# RPI_HAT_AMP_TAS5756_02.net
KiCad netlist of a schematic drawn in Altium Designer
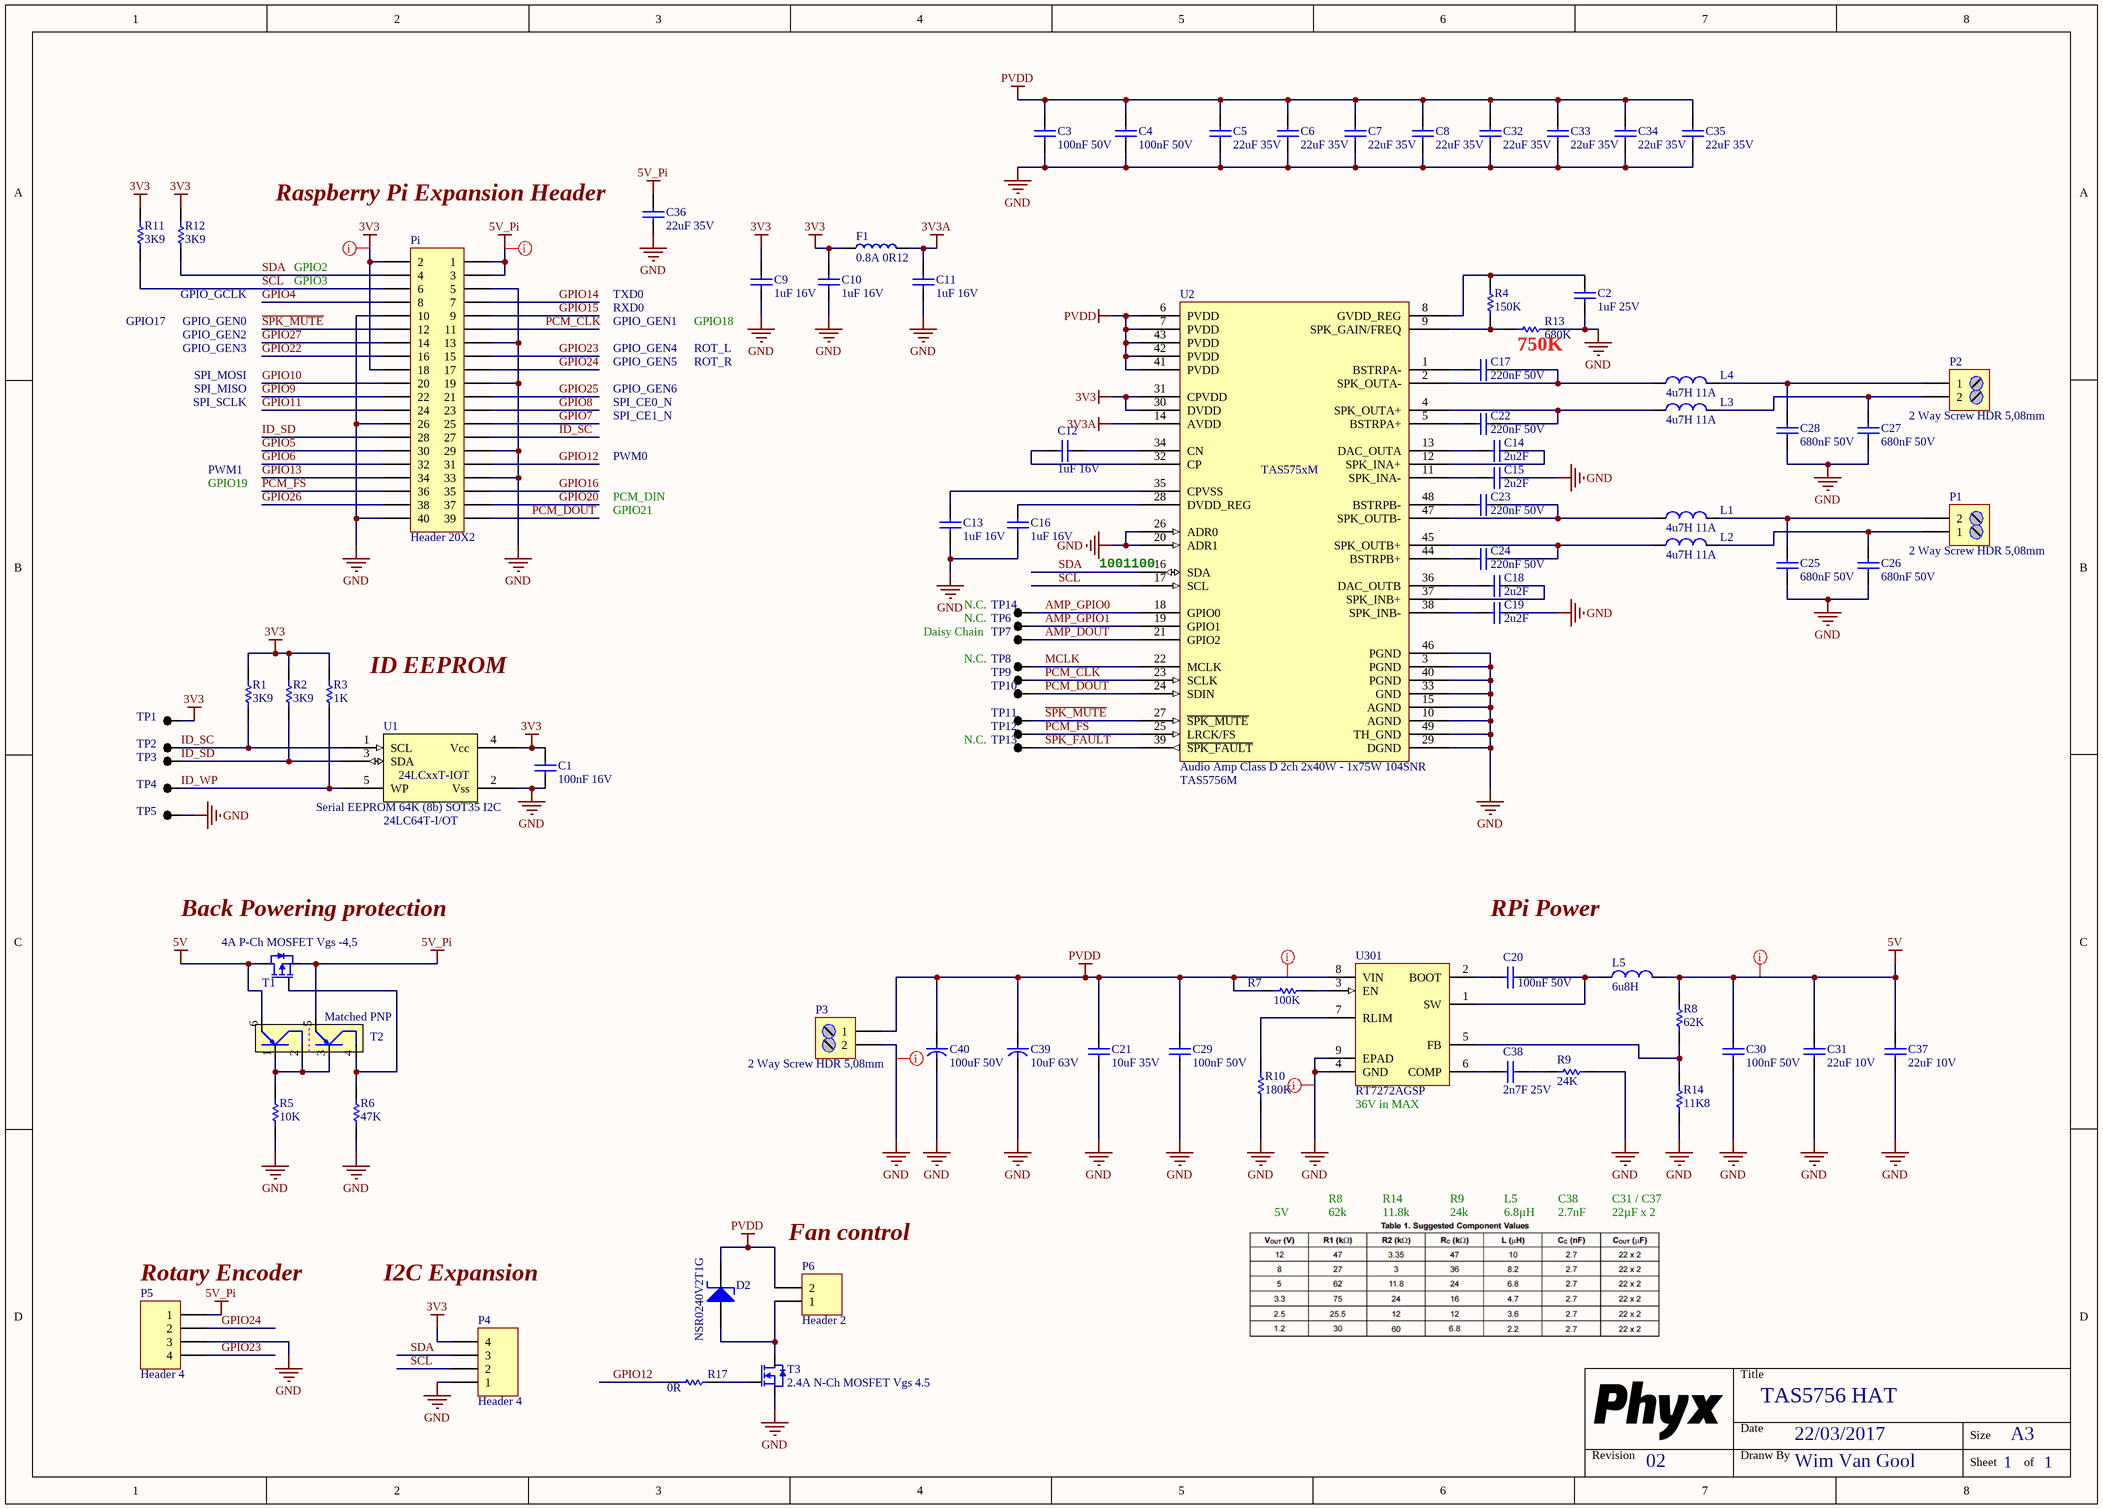
[diagram p0: RPI_HAT_AMP_TAS5756_02.SchDoc]

(export (version "E")
  (design (tool "Eeschema 10.0.6"))
  (components
    (comp (ref "C1")
      (value "100nF 16V")
      (footprint "C0603_N")
      (description "Capacitor Ceramic")
      (fields (field (name "Comment") "CAP_CERAMIC"))
      (libsource (lib "Phyx_Components") (part "CAP_CERAMIC"))
    )
    (comp (ref "C2")
      (value "1uF 25V")
      (footprint "C0805_N")
      (description "Capacitor Ceramic")
      (fields (field (name "Comment") "CAP_CERAMIC"))
      (libsource (lib "Phyx_Components") (part "CAP_CERAMIC"))
    )
    (comp (ref "C3")
      (value "100nF 50V")
      (footprint "C0805_N")
      (description "Capacitor Ceramic")
      (fields (field (name "Comment") "CAP_CERAMIC"))
      (libsource (lib "Phyx_Components") (part "CAP_CERAMIC"))
    )
    (comp (ref "C4")
      (value "100nF 50V")
      (footprint "C0805_N")
      (description "Capacitor Ceramic")
      (fields (field (name "Comment") "CAP_CERAMIC"))
      (libsource (lib "Phyx_Components") (part "CAP_CERAMIC"))
    )
    (comp (ref "C5")
      (value "22uF 35V")
      (footprint "C1206_N")
      (description "Capacitor Ceramic")
      (fields (field (name "Comment") "CAP_CERAMIC"))
      (libsource (lib "Phyx_Components") (part "CAP_CERAMIC"))
    )
    (comp (ref "C6")
      (value "22uF 35V")
      (footprint "C1206_N")
      (description "Capacitor Ceramic")
      (fields (field (name "Comment") "CAP_CERAMIC"))
      (libsource (lib "Phyx_Components") (part "CAP_CERAMIC"))
    )
    (comp (ref "C7")
      (value "22uF 35V")
      (footprint "C1206_N")
      (description "Capacitor Ceramic")
      (fields (field (name "Comment") "CAP_CERAMIC"))
      (libsource (lib "Phyx_Components") (part "CAP_CERAMIC"))
    )
    (comp (ref "C8")
      (value "22uF 35V")
      (footprint "C1206_N")
      (description "Capacitor Ceramic")
      (fields (field (name "Comment") "CAP_CERAMIC"))
      (libsource (lib "Phyx_Components") (part "CAP_CERAMIC"))
    )
    (comp (ref "C9")
      (value "1uF 16V")
      (footprint "C0603_N")
      (description "Capacitor Ceramic")
      (fields (field (name "Comment") "CAP_CERAMIC"))
      (libsource (lib "Phyx_Components") (part "CAP_CERAMIC"))
    )
    (comp (ref "C10")
      (value "1uF 16V")
      (footprint "C0603_N")
      (description "Capacitor Ceramic")
      (fields (field (name "Comment") "CAP_CERAMIC"))
      (libsource (lib "Phyx_Components") (part "CAP_CERAMIC"))
    )
    (comp (ref "C11")
      (value "1uF 16V")
      (footprint "C0603_N")
      (description "Capacitor Ceramic")
      (fields (field (name "Comment") "CAP_CERAMIC"))
      (libsource (lib "Phyx_Components") (part "CAP_CERAMIC"))
    )
    (comp (ref "C12")
      (value "1uF 16V")
      (footprint "C0603_N")
      (description "Capacitor Ceramic")
      (fields (field (name "Comment") "CAP_CERAMIC"))
      (libsource (lib "Phyx_Components") (part "CAP_CERAMIC"))
    )
    (comp (ref "C13")
      (value "1uF 16V")
      (footprint "C0603_N")
      (description "Capacitor Ceramic")
      (fields (field (name "Comment") "CAP_CERAMIC"))
      (libsource (lib "Phyx_Components") (part "CAP_CERAMIC"))
    )
    (comp (ref "C14")
      (value "2u2F")
      (footprint "C0805_N")
      (description "Capacitor Ceramic")
      (fields (field (name "Comment") "CAP_CERAMIC"))
      (libsource (lib "Phyx_Components") (part "CAP_CERAMIC"))
    )
    (comp (ref "C15")
      (value "2u2F")
      (footprint "C0805_N")
      (description "Capacitor Ceramic")
      (fields (field (name "Comment") "CAP_CERAMIC"))
      (libsource (lib "Phyx_Components") (part "CAP_CERAMIC"))
    )
    (comp (ref "C16")
      (value "1uF 16V")
      (footprint "C0603_N")
      (description "Capacitor Ceramic")
      (fields (field (name "Comment") "CAP_CERAMIC"))
      (libsource (lib "Phyx_Components") (part "CAP_CERAMIC"))
    )
    (comp (ref "C17")
      (value "220nF 50V")
      (footprint "C0805_N")
      (description "Capacitor Ceramic")
      (fields (field (name "Comment") "CAP_CERAMIC"))
      (libsource (lib "Phyx_Components") (part "CAP_CERAMIC"))
    )
    (comp (ref "C18")
      (value "2u2F")
      (footprint "C0805_N")
      (description "Capacitor Ceramic")
      (fields (field (name "Comment") "CAP_CERAMIC"))
      (libsource (lib "Phyx_Components") (part "CAP_CERAMIC"))
    )
    (comp (ref "C19")
      (value "2u2F")
      (footprint "C0805_N")
      (description "Capacitor Ceramic")
      (fields (field (name "Comment") "CAP_CERAMIC"))
      (libsource (lib "Phyx_Components") (part "CAP_CERAMIC"))
    )
    (comp (ref "C20")
      (value "100nF 50V")
      (footprint "C0603_N")
      (description "Capacitor Ceramic")
      (fields (field (name "Comment") "CAP_CERAMIC"))
      (libsource (lib "Phyx_Components") (part "CAP_CERAMIC"))
    )
    (comp (ref "C21")
      (value "10uF 35V")
      (footprint "C1206_N")
      (description "CAP # 10uF 35V 1206 X5R")
      (fields (field (name "Comment") "CAP_CERAMIC"))
      (libsource (lib "Phyx_Components") (part "CAP_CERAMIC"))
    )
    (comp (ref "C22")
      (value "220nF 50V")
      (footprint "C0805_N")
      (description "Capacitor Ceramic")
      (fields (field (name "Comment") "CAP_CERAMIC"))
      (libsource (lib "Phyx_Components") (part "CAP_CERAMIC"))
    )
    (comp (ref "C23")
      (value "220nF 50V")
      (footprint "C0805_N")
      (description "Capacitor Ceramic")
      (fields (field (name "Comment") "CAP_CERAMIC"))
      (libsource (lib "Phyx_Components") (part "CAP_CERAMIC"))
    )
    (comp (ref "C24")
      (value "220nF 50V")
      (footprint "C0805_N")
      (description "Capacitor Ceramic")
      (fields (field (name "Comment") "CAP_CERAMIC"))
      (libsource (lib "Phyx_Components") (part "CAP_CERAMIC"))
    )
    (comp (ref "C25")
      (value "680nF 50V")
      (footprint "C0805_N")
      (description "Capacitor Ceramic")
      (fields (field (name "Comment") "CAP_CERAMIC"))
      (libsource (lib "Phyx_Components") (part "CAP_CERAMIC"))
    )
    (comp (ref "C26")
      (value "680nF 50V")
      (footprint "C0805_N")
      (description "Capacitor Ceramic")
      (fields (field (name "Comment") "CAP_CERAMIC"))
      (libsource (lib "Phyx_Components") (part "CAP_CERAMIC"))
    )
    (comp (ref "C27")
      (value "680nF 50V")
      (footprint "C0805_N")
      (description "Capacitor Ceramic")
      (fields (field (name "Comment") "CAP_CERAMIC"))
      (libsource (lib "Phyx_Components") (part "CAP_CERAMIC"))
    )
    (comp (ref "C28")
      (value "680nF 50V")
      (footprint "C0805_N")
      (description "Capacitor Ceramic")
      (fields (field (name "Comment") "CAP_CERAMIC"))
      (libsource (lib "Phyx_Components") (part "CAP_CERAMIC"))
    )
    (comp (ref "C29")
      (value "100nF 50V")
      (footprint "C0603_N")
      (description "Capacitor Ceramic")
      (fields (field (name "Comment") "CAP_CERAMIC"))
      (libsource (lib "Phyx_Components") (part "CAP_CERAMIC"))
    )
    (comp (ref "C30")
      (value "100nF 50V")
      (footprint "C0603_N")
      (description "Capacitor Ceramic")
      (fields (field (name "Comment") "CAP_CERAMIC"))
      (libsource (lib "Phyx_Components") (part "CAP_CERAMIC"))
    )
    (comp (ref "C31")
      (value "22uF 10V")
      (footprint "C1210_N")
      (description "Capacitor Ceramic")
      (fields (field (name "Comment") "CAP_CERAMIC"))
      (libsource (lib "Phyx_Components") (part "CAP_CERAMIC"))
    )
    (comp (ref "C32")
      (value "22uF 35V")
      (footprint "C1206_N")
      (description "Capacitor Ceramic")
      (fields (field (name "Comment") "CAP_CERAMIC"))
      (libsource (lib "Phyx_Components") (part "CAP_CERAMIC"))
    )
    (comp (ref "C33")
      (value "22uF 35V")
      (footprint "C1206_N")
      (description "Capacitor Ceramic")
      (fields (field (name "Comment") "CAP_CERAMIC"))
      (libsource (lib "Phyx_Components") (part "CAP_CERAMIC"))
    )
    (comp (ref "C34")
      (value "22uF 35V")
      (footprint "C1206_N")
      (description "Capacitor Ceramic")
      (fields (field (name "Comment") "CAP_CERAMIC"))
      (libsource (lib "Phyx_Components") (part "CAP_CERAMIC"))
    )
    (comp (ref "C35")
      (value "22uF 35V")
      (footprint "C1206_N")
      (description "Capacitor Ceramic")
      (fields (field (name "Comment") "CAP_CERAMIC"))
      (libsource (lib "Phyx_Components") (part "CAP_CERAMIC"))
    )
    (comp (ref "C36")
      (value "22uF 35V")
      (footprint "C1206_N")
      (description "Capacitor Ceramic")
      (fields (field (name "Comment") "CAP_CERAMIC"))
      (libsource (lib "Phyx_Components") (part "CAP_CERAMIC"))
    )
    (comp (ref "C37")
      (value "22uF 10V")
      (footprint "C1210_N")
      (description "Capacitor Ceramic")
      (fields (field (name "Comment") "CAP_CERAMIC"))
      (libsource (lib "Phyx_Components") (part "CAP_CERAMIC"))
    )
    (comp (ref "C38")
      (value "2n7F 25V")
      (footprint "C0603_N")
      (description "Capacitor Ceramic")
      (fields (field (name "Comment") "CAP_CERAMIC"))
      (libsource (lib "Phyx_Components") (part "CAP_CERAMIC"))
    )
    (comp (ref "C39")
      (value "10uF 63V")
      (footprint "C_5x11_2mm")
      (description "CAP 10uF 63V 5x11mm")
      (fields (field (name "Comment") "CAP_POL"))
      (libsource (lib "Phyx_Components") (part "CAP_POL"))
    )
    (comp (ref "C40")
      (value "100uF 50V")
      (footprint "C_8x11.5_3.5mm")
      (description "CAP 100uF 50V 8x11mm")
      (fields (field (name "Comment") "CAP_POL"))
      (libsource (lib "Phyx_Components") (part "CAP_POL"))
    )
    (comp (ref "D2")
      (value "NSR0240V2T1G")
      (footprint "ON_SOD-523")
      (description "=Description")
      (fields (field (name "Comment") "NSR0240V2T1G Schottky ULTRAFAST, 200MA, 40V"))
      (libsource (lib "Phyx_Components") (part "Schottky_CA"))
    )
    (comp (ref "F1")
      (value "0.8A 0R12")
      (footprint "L0805")
      (fields (field (name "Comment") "FERRITE"))
      (libsource (lib "Phyx_Components") (part "FERRITE"))
    )
    (comp (ref "L1")
      (value "4u7H 11A")
      (footprint "XAL6060-472")
      (fields (field (name "Comment") "XAL6060-472MEC"))
      (libsource (lib "Phyx_Components") (part "INDUCTOR"))
    )
    (comp (ref "L2")
      (value "4u7H 11A")
      (footprint "XAL6060-472")
      (fields (field (name "Comment") "XAL6060-472MEC"))
      (libsource (lib "Phyx_Components") (part "INDUCTOR"))
    )
    (comp (ref "L3")
      (value "4u7H 11A")
      (footprint "XAL6060-472")
      (fields (field (name "Comment") "XAL6060-472MEC"))
      (libsource (lib "Phyx_Components") (part "INDUCTOR"))
    )
    (comp (ref "L4")
      (value "4u7H 11A")
      (footprint "XAL6060-472")
      (fields (field (name "Comment") "XAL6060-472MEC"))
      (libsource (lib "Phyx_Components") (part "INDUCTOR"))
    )
    (comp (ref "L5")
      (value "6u8H")
      (footprint "SNL_SWPA4020")
      (fields (field (name "Comment") "SWPA4020S6R8MT"))
      (libsource (lib "Phyx_Components") (part "INDUCTOR"))
    )
    (comp (ref "P1")
      (value "2 Way Screw HDR 5,08mm")
      (footprint "TERM_BLK-0508-2-90")
      (libsource (lib "") (part "TERM_BLCK_2_2"))
    )
    (comp (ref "P2")
      (value "2 Way Screw HDR 5,08mm")
      (footprint "TERM_BLK-0508-2-90")
      (libsource (lib "") (part "TERM_BLCK_2_1"))
    )
    (comp (ref "P3")
      (value "2 Way Screw HDR 5,08mm")
      (footprint "TERM_BLK-0508-2-90")
      (libsource (lib "Phyx_Components") (part "TERM_BLCK_2"))
    )
    (comp (ref "P4") (value "Header 4") (footprint "HDR1X4") (libsource (lib "") (part "Header 4_1")))
    (comp (ref "P5")
      (value "Header 4")
      (footprint "HDR1X4")
      (libsource (lib "Phyx_Components") (part "Header 4"))
    )
    (comp (ref "P6")
      (value "Header 2")
      (footprint "HDR1X2")
      (libsource (lib "Phyx_Components") (part "Header 2"))
    )
    (comp (ref "Pi")
      (value "Header 20X2")
      (footprint "RCPT2X20")
      (description "=Description")
      (libsource (lib "Phyx_Components") (part "Header 20X2"))
    )
    (comp (ref "R1")
      (value "3K9")
      (footprint "R0603_N")
      (fields (field (name "Comment") "RESISTOR"))
      (libsource (lib "Phyx_Components") (part "RESISTOR"))
    )
    (comp (ref "R2")
      (value "3K9")
      (footprint "R0603_N")
      (fields (field (name "Comment") "RESISTOR"))
      (libsource (lib "Phyx_Components") (part "RESISTOR"))
    )
    (comp (ref "R3")
      (value "1K")
      (footprint "R0603_N")
      (fields (field (name "Comment") "RESISTOR"))
      (libsource (lib "Phyx_Components") (part "RESISTOR"))
    )
    (comp (ref "R4")
      (value "150K")
      (footprint "R0603_N")
      (fields (field (name "Comment") "RESISTOR"))
      (libsource (lib "Phyx_Components") (part "RESISTOR"))
    )
    (comp (ref "R5")
      (value "10K")
      (footprint "R0603_N")
      (fields (field (name "Comment") "RESISTOR"))
      (libsource (lib "Phyx_Components") (part "RESISTOR"))
    )
    (comp (ref "R6")
      (value "47K")
      (footprint "R0603_N")
      (fields (field (name "Comment") "RESISTOR"))
      (libsource (lib "Phyx_Components") (part "RESISTOR"))
    )
    (comp (ref "R7")
      (value "100K")
      (footprint "R0603_N")
      (fields (field (name "Comment") "RESISTOR"))
      (libsource (lib "Phyx_Components") (part "RESISTOR"))
    )
    (comp (ref "R8")
      (value "62K")
      (footprint "R0603_N")
      (fields (field (name "Comment") "RESISTOR"))
      (libsource (lib "Phyx_Components") (part "RESISTOR"))
    )
    (comp (ref "R9")
      (value "24K")
      (footprint "R0603_N")
      (fields (field (name "Comment") "RESISTOR"))
      (libsource (lib "Phyx_Components") (part "RESISTOR"))
    )
    (comp (ref "R10")
      (value "180K")
      (footprint "R0603_N")
      (fields (field (name "Comment") "RESISTOR"))
      (libsource (lib "Phyx_Components") (part "RESISTOR"))
    )
    (comp (ref "R11")
      (value "3K9")
      (footprint "R0603_N")
      (fields (field (name "Comment") "RESISTOR"))
      (libsource (lib "Phyx_Components") (part "RESISTOR"))
    )
    (comp (ref "R12")
      (value "3K9")
      (footprint "R0603_N")
      (fields (field (name "Comment") "RESISTOR"))
      (libsource (lib "Phyx_Components") (part "RESISTOR"))
    )
    (comp (ref "R13")
      (value "680K")
      (footprint "R0603_N")
      (fields (field (name "Comment") "RESISTOR"))
      (libsource (lib "Phyx_Components") (part "RESISTOR"))
    )
    (comp (ref "R14")
      (value "11K8")
      (footprint "R0603_N")
      (fields (field (name "Comment") "RESISTOR"))
      (libsource (lib "Phyx_Components") (part "RESISTOR"))
    )
    (comp (ref "R17")
      (value "0R")
      (footprint "R0603_N")
      (fields (field (name "Comment") "RESISTOR"))
      (libsource (lib "Phyx_Components") (part "RESISTOR"))
    )
    (comp (ref "T1")
      (value "4A P-Ch MOSFET Vgs -4,5")
      (footprint "SOT23-3")
      (description "=Description")
      (libsource (lib "Phyx_Components") (part "P_MOSFET_GSD"))
    )
    (comp (ref "T2")
      (value "Matched PNP")
      (footprint "SOT23-6")
      (libsource (lib "Phyx_Components") (part "DMMT5401"))
    )
    (comp (ref "T3")
      (value "2.4A N-Ch MOSFET Vgs 4.5")
      (footprint "SOT23-3")
      (libsource (lib "Phyx_Components") (part "N_MOSFET_GSD"))
    )
    (comp (ref "TP1")
      (value "TEST_PAD")
      (footprint "TP_1.2mm_0.6mm")
      (libsource (lib "Phyx_Components") (part "TEST_PAD"))
    )
    (comp (ref "TP2")
      (value "TEST_PAD")
      (footprint "TP_1.2mm_0.6mm")
      (libsource (lib "Phyx_Components") (part "TEST_PAD"))
    )
    (comp (ref "TP3")
      (value "TEST_PAD")
      (footprint "TP_1.2mm_0.6mm")
      (libsource (lib "Phyx_Components") (part "TEST_PAD"))
    )
    (comp (ref "TP4")
      (value "TEST_PAD")
      (footprint "TP_1.2mm_0.6mm")
      (libsource (lib "Phyx_Components") (part "TEST_PAD"))
    )
    (comp (ref "TP5")
      (value "TEST_PAD")
      (footprint "TP_1.2mm_0.6mm")
      (libsource (lib "Phyx_Components") (part "TEST_PAD"))
    )
    (comp (ref "TP6")
      (value "TEST_PAD")
      (footprint "TP_0.4mm")
      (libsource (lib "Phyx_Components") (part "TEST_PAD"))
    )
    (comp (ref "TP7")
      (value "TEST_PAD")
      (footprint "TP_1.2mm_0.6mm")
      (libsource (lib "Phyx_Components") (part "TEST_PAD"))
    )
    (comp (ref "TP8")
      (value "TEST_PAD")
      (footprint "TP_0.4mm")
      (libsource (lib "Phyx_Components") (part "TEST_PAD"))
    )
    (comp (ref "TP9")
      (value "TEST_PAD")
      (footprint "TP_0.4mm")
      (libsource (lib "Phyx_Components") (part "TEST_PAD"))
    )
    (comp (ref "TP10")
      (value "TEST_PAD")
      (footprint "TP_1.2mm_0.6mm")
      (libsource (lib "Phyx_Components") (part "TEST_PAD"))
    )
    (comp (ref "TP11")
      (value "TEST_PAD")
      (footprint "TP_0.4mm")
      (libsource (lib "Phyx_Components") (part "TEST_PAD"))
    )
    (comp (ref "TP12")
      (value "TEST_PAD")
      (footprint "TP_0.4mm")
      (libsource (lib "Phyx_Components") (part "TEST_PAD"))
    )
    (comp (ref "TP13")
      (value "TEST_PAD")
      (footprint "TP_0.4mm")
      (libsource (lib "Phyx_Components") (part "TEST_PAD"))
    )
    (comp (ref "TP14")
      (value "TEST_PAD")
      (footprint "TP_0.4mm")
      (libsource (lib "Phyx_Components") (part "TEST_PAD"))
    )
    (comp (ref "U1")
      (value "Serial EEPROM 64K (8b) SOT35 I2C")
      (footprint "SOT23-5")
      (description "=Description")
      (fields (field (name "ALTIUM_VALUE") "24LC64T-I/OT"))
      (libsource (lib "Phyx_Components") (part "24LCxxT-IOT"))
    )
    (comp (ref "U2")
      (value "Audio Amp Class D 2ch 2x40W - 1x75W 104SNR")
      (footprint "TI-DCA-R-PDSO-G48")
      (description "=Description")
      (fields (field (name "ALTIUM_VALUE") "TAS5756M"))
      (libsource (lib "Phyx_Components") (part "TAS575xM"))
    )
    (comp (ref "U301")
      (value "RT7272AGSP")
      (footprint "SOIC_N_8_TH")
      (description "=Description")
      (fields (field (name "Comment") "Buck 3A 36Vin sync"))
      (libsource (lib "Phyx_Components") (part "RT7272xGSP"))
    )
  )
  (nets
    (net (code "1") (name "/AMP_DOUT") (class "Default")
      (node (ref "TP7") (pin "1") (pinfunction "1_1") (pintype "passive"))
      (node (ref "U2") (pin "21") (pinfunction "GPIO2_21") (pintype "passive"))
    )
    (net (code "2") (name "/AMP_GPIO0") (class "Default")
      (node (ref "TP14") (pin "1") (pinfunction "1_1") (pintype "passive"))
      (node (ref "U2") (pin "18") (pinfunction "GPIO0_18") (pintype "passive"))
    )
    (net (code "3") (name "/AMP_GPIO1") (class "Default")
      (node (ref "TP6") (pin "1") (pinfunction "1_1") (pintype "passive"))
      (node (ref "U2") (pin "19") (pinfunction "GPIO1_19") (pintype "passive"))
    )
    (net (code "4") (name "/GPIO4") (class "Default")
      (node (ref "Pi") (pin "8") (pinfunction "8_8") (pintype "passive"))
    )
    (net (code "5") (name "/GPIO5") (class "Default")
      (node (ref "Pi") (pin "30") (pinfunction "30_30") (pintype "passive"))
    )
    (net (code "6") (name "/GPIO6") (class "Default")
      (node (ref "Pi") (pin "32") (pinfunction "32_32") (pintype "passive"))
    )
    (net (code "7") (name "/GPIO7") (class "Default")
      (node (ref "Pi") (pin "25") (pinfunction "25_25") (pintype "passive"))
    )
    (net (code "8") (name "/GPIO8") (class "Default")
      (node (ref "Pi") (pin "23") (pinfunction "23_23") (pintype "passive"))
    )
    (net (code "9") (name "/GPIO9") (class "Default")
      (node (ref "Pi") (pin "22") (pinfunction "22_22") (pintype "passive"))
    )
    (net (code "10") (name "/GPIO10") (class "Default")
      (node (ref "Pi") (pin "20") (pinfunction "20_20") (pintype "passive"))
    )
    (net (code "11") (name "/GPIO11") (class "Default")
      (node (ref "Pi") (pin "24") (pinfunction "24_24") (pintype "passive"))
    )
    (net (code "12") (name "/GPIO12") (class "Default")
      (node (ref "Pi") (pin "31") (pinfunction "31_31") (pintype "passive"))
      (node (ref "R17") (pin "2") (pinfunction "2_2") (pintype "passive"))
    )
    (net (code "13") (name "/GPIO13") (class "Default")
      (node (ref "Pi") (pin "34") (pinfunction "34_34") (pintype "passive"))
    )
    (net (code "14") (name "/GPIO14") (class "Default")
      (node (ref "Pi") (pin "7") (pinfunction "7_7") (pintype "passive"))
    )
    (net (code "15") (name "/GPIO15") (class "Default")
      (node (ref "Pi") (pin "9") (pinfunction "9_9") (pintype "passive"))
    )
    (net (code "16") (name "/GPIO16") (class "Default")
      (node (ref "Pi") (pin "35") (pinfunction "35_35") (pintype "passive"))
    )
    (net (code "17") (name "/GPIO20") (class "Default")
      (node (ref "Pi") (pin "37") (pinfunction "37_37") (pintype "passive"))
    )
    (net (code "18") (name "/GPIO22") (class "Default")
      (node (ref "Pi") (pin "16") (pinfunction "16_16") (pintype "passive"))
    )
    (net (code "19") (name "/GPIO23") (class "Default")
      (node (ref "P5") (pin "4") (pinfunction "4_4") (pintype "passive"))
      (node (ref "Pi") (pin "15") (pinfunction "15_15") (pintype "passive"))
    )
    (net (code "20") (name "/GPIO24") (class "Default")
      (node (ref "P5") (pin "2") (pinfunction "2_2") (pintype "passive"))
      (node (ref "Pi") (pin "17") (pinfunction "17_17") (pintype "passive"))
    )
    (net (code "21") (name "/GPIO25") (class "Default")
      (node (ref "Pi") (pin "21") (pinfunction "21_21") (pintype "passive"))
    )
    (net (code "22") (name "/GPIO26") (class "Default")
      (node (ref "Pi") (pin "38") (pinfunction "38_38") (pintype "passive"))
    )
    (net (code "23") (name "/GPIO27") (class "Default")
      (node (ref "Pi") (pin "14") (pinfunction "14_14") (pintype "passive"))
    )
    (net (code "24") (name "/ID_SC") (class "Default")
      (node (ref "Pi") (pin "27") (pinfunction "27_27") (pintype "passive"))
      (node (ref "R1") (pin "2") (pinfunction "2_2") (pintype "passive"))
      (node (ref "TP2") (pin "1") (pinfunction "1_1") (pintype "passive"))
      (node (ref "U1") (pin "1") (pinfunction "SCL_1") (pintype "input"))
    )
    (net (code "25") (name "/ID_SD") (class "Default")
      (node (ref "Pi") (pin "28") (pinfunction "28_28") (pintype "passive"))
      (node (ref "R2") (pin "2") (pinfunction "2_2") (pintype "passive"))
      (node (ref "TP3") (pin "1") (pinfunction "1_1") (pintype "passive"))
      (node (ref "U1") (pin "3") (pinfunction "SDA_3") (pintype "bidirectional"))
    )
    (net (code "26") (name "/ID_WP") (class "Default")
      (node (ref "R3") (pin "2") (pinfunction "2_2") (pintype "passive"))
      (node (ref "TP4") (pin "1") (pinfunction "1_1") (pintype "passive"))
      (node (ref "U1") (pin "5") (pinfunction "WP_5") (pintype "passive"))
    )
    (net (code "27") (name "/MCLK") (class "Default")
      (node (ref "TP8") (pin "1") (pinfunction "1_1") (pintype "passive"))
      (node (ref "U2") (pin "22") (pinfunction "MCLK_22") (pintype "passive"))
    )
    (net (code "28") (name "/PCM_CLK") (class "Default")
      (node (ref "Pi") (pin "11") (pinfunction "11_11") (pintype "passive"))
      (node (ref "TP9") (pin "1") (pinfunction "1_1") (pintype "passive"))
      (node (ref "U2") (pin "23") (pinfunction "SCLK_23") (pintype "input"))
    )
    (net (code "29") (name "/PCM_DOUT") (class "Default")
      (node (ref "Pi") (pin "39") (pinfunction "39_39") (pintype "passive"))
      (node (ref "TP10") (pin "1") (pinfunction "1_1") (pintype "passive"))
      (node (ref "U2") (pin "24") (pinfunction "SDIN_24") (pintype "input"))
    )
    (net (code "30") (name "/PCM_FS") (class "Default")
      (node (ref "Pi") (pin "36") (pinfunction "36_36") (pintype "passive"))
      (node (ref "TP12") (pin "1") (pinfunction "1_1") (pintype "passive"))
      (node (ref "U2") (pin "25") (pinfunction "LRCK/FS_25") (pintype "input"))
    )
    (net (code "31") (name "/SCL") (class "Default")
      (node (ref "P4") (pin "2") (pinfunction "2_2") (pintype "passive"))
      (node (ref "Pi") (pin "6") (pinfunction "6_6") (pintype "passive"))
      (node (ref "R11") (pin "2") (pinfunction "2_2") (pintype "passive"))
      (node (ref "U2") (pin "17") (pinfunction "SCL_17") (pintype "input"))
    )
    (net (code "32") (name "/SDA") (class "Default")
      (node (ref "P4") (pin "3") (pinfunction "3_3") (pintype "passive"))
      (node (ref "Pi") (pin "4") (pinfunction "4_4") (pintype "passive"))
      (node (ref "R12") (pin "2") (pinfunction "2_2") (pintype "passive"))
      (node (ref "U2") (pin "16") (pinfunction "SDA_16") (pintype "bidirectional"))
    )
    (net (code "33") (name "/~{SPK_FAULT}") (class "Default")
      (node (ref "TP13") (pin "1") (pinfunction "1_1") (pintype "passive"))
      (node (ref "U2") (pin "39") (pinfunction "~{SPK_FAULT}_39") (pintype "output"))
    )
    (net (code "34") (name "/~{SPK_MUTE}") (class "Default")
      (node (ref "Pi") (pin "12") (pinfunction "12_12") (pintype "passive"))
      (node (ref "TP11") (pin "1") (pinfunction "1_1") (pintype "passive"))
      (node (ref "U2") (pin "27") (pinfunction "~{SPK_MUTE}_27") (pintype "input"))
    )
    (net (code "35") (name "3V3") (class "Default")
      (node (ref "C1") (pin "1") (pinfunction "1_1") (pintype "passive"))
      (node (ref "C10") (pin "1") (pinfunction "1_1") (pintype "passive"))
      (node (ref "C9") (pin "1") (pinfunction "1_1") (pintype "passive"))
      (node (ref "F1") (pin "1") (pinfunction "1_1") (pintype "passive"))
      (node (ref "P4") (pin "4") (pinfunction "4_4") (pintype "passive"))
      (node (ref "Pi") (pin "18") (pinfunction "18_18") (pintype "passive"))
      (node (ref "Pi") (pin "2") (pinfunction "2_2") (pintype "passive"))
      (node (ref "R1") (pin "1") (pinfunction "1_1") (pintype "passive"))
      (node (ref "R11") (pin "1") (pinfunction "1_1") (pintype "passive"))
      (node (ref "R12") (pin "1") (pinfunction "1_1") (pintype "passive"))
      (node (ref "R2") (pin "1") (pinfunction "1_1") (pintype "passive"))
      (node (ref "R3") (pin "1") (pinfunction "1_1") (pintype "passive"))
      (node (ref "TP1") (pin "1") (pinfunction "1_1") (pintype "passive"))
      (node (ref "U1") (pin "4") (pinfunction "Vcc_4") (pintype "passive"))
      (node (ref "U2") (pin "30") (pinfunction "DVDD_30") (pintype "power_in"))
      (node (ref "U2") (pin "31") (pinfunction "CPVDD_31") (pintype "passive"))
    )
    (net (code "36") (name "3V3A") (class "Default")
      (node (ref "C11") (pin "1") (pinfunction "1_1") (pintype "passive"))
      (node (ref "F1") (pin "2") (pinfunction "2_2") (pintype "passive"))
      (node (ref "U2") (pin "14") (pinfunction "AVDD_14") (pintype "power_in"))
    )
    (net (code "37") (name "5V") (class "Default")
      (node (ref "C30") (pin "1") (pinfunction "1_1") (pintype "passive"))
      (node (ref "C31") (pin "1") (pinfunction "1_1") (pintype "passive"))
      (node (ref "C37") (pin "1") (pinfunction "1_1") (pintype "passive"))
      (node (ref "L5") (pin "2") (pinfunction "2_2") (pintype "passive"))
      (node (ref "R8") (pin "1") (pinfunction "1_1") (pintype "passive"))
      (node (ref "T1") (pin "3") (pinfunction "D_3") (pintype "passive"))
      (node (ref "T2") (pin "6") (pinfunction "E_6") (pintype "passive"))
    )
    (net (code "38") (name "5V_Pi") (class "Default")
      (node (ref "C36") (pin "1") (pinfunction "1_1") (pintype "passive"))
      (node (ref "P5") (pin "1") (pinfunction "1_1") (pintype "passive"))
      (node (ref "Pi") (pin "1") (pinfunction "1_1") (pintype "passive"))
      (node (ref "Pi") (pin "3") (pinfunction "3_3") (pintype "passive"))
      (node (ref "T1") (pin "2") (pinfunction "S_2") (pintype "passive"))
      (node (ref "T2") (pin "5") (pinfunction "E_5") (pintype "passive"))
    )
    (net (code "39") (name "GND") (class "Default")
      (node (ref "C1") (pin "2") (pinfunction "2_2") (pintype "passive"))
      (node (ref "C10") (pin "2") (pinfunction "2_2") (pintype "passive"))
      (node (ref "C11") (pin "2") (pinfunction "2_2") (pintype "passive"))
      (node (ref "C13") (pin "2") (pinfunction "2_2") (pintype "passive"))
      (node (ref "C15") (pin "1") (pinfunction "1_1") (pintype "passive"))
      (node (ref "C16") (pin "2") (pinfunction "2_2") (pintype "passive"))
      (node (ref "C19") (pin "1") (pinfunction "1_1") (pintype "passive"))
      (node (ref "C2") (pin "2") (pinfunction "2_2") (pintype "passive"))
      (node (ref "C21") (pin "2") (pinfunction "2_2") (pintype "passive"))
      (node (ref "C25") (pin "1") (pinfunction "1_1") (pintype "passive"))
      (node (ref "C26") (pin "1") (pinfunction "1_1") (pintype "passive"))
      (node (ref "C27") (pin "1") (pinfunction "1_1") (pintype "passive"))
      (node (ref "C28") (pin "1") (pinfunction "1_1") (pintype "passive"))
      (node (ref "C29") (pin "2") (pinfunction "2_2") (pintype "passive"))
      (node (ref "C3") (pin "2") (pinfunction "2_2") (pintype "passive"))
      (node (ref "C30") (pin "2") (pinfunction "2_2") (pintype "passive"))
      (node (ref "C31") (pin "2") (pinfunction "2_2") (pintype "passive"))
      (node (ref "C32") (pin "2") (pinfunction "2_2") (pintype "passive"))
      (node (ref "C33") (pin "2") (pinfunction "2_2") (pintype "passive"))
      (node (ref "C34") (pin "2") (pinfunction "2_2") (pintype "passive"))
      (node (ref "C35") (pin "2") (pinfunction "2_2") (pintype "passive"))
      (node (ref "C36") (pin "2") (pinfunction "2_2") (pintype "passive"))
      (node (ref "C37") (pin "2") (pinfunction "2_2") (pintype "passive"))
      (node (ref "C39") (pin "2") (pinfunction "2_2") (pintype "passive"))
      (node (ref "C4") (pin "2") (pinfunction "2_2") (pintype "passive"))
      (node (ref "C40") (pin "2") (pinfunction "2_2") (pintype "passive"))
      (node (ref "C5") (pin "2") (pinfunction "2_2") (pintype "passive"))
      (node (ref "C6") (pin "2") (pinfunction "2_2") (pintype "passive"))
      (node (ref "C7") (pin "2") (pinfunction "2_2") (pintype "passive"))
      (node (ref "C8") (pin "2") (pinfunction "2_2") (pintype "passive"))
      (node (ref "C9") (pin "2") (pinfunction "2_2") (pintype "passive"))
      (node (ref "P3") (pin "2") (pinfunction "2_2") (pintype "passive"))
      (node (ref "P4") (pin "1") (pinfunction "1_1") (pintype "passive"))
      (node (ref "P5") (pin "3") (pinfunction "3_3") (pintype "passive"))
      (node (ref "Pi") (pin "10") (pinfunction "10_10") (pintype "passive"))
      (node (ref "Pi") (pin "13") (pinfunction "13_13") (pintype "passive"))
      (node (ref "Pi") (pin "19") (pinfunction "19_19") (pintype "passive"))
      (node (ref "Pi") (pin "26") (pinfunction "26_26") (pintype "passive"))
      (node (ref "Pi") (pin "29") (pinfunction "29_29") (pintype "passive"))
      (node (ref "Pi") (pin "33") (pinfunction "33_33") (pintype "passive"))
      (node (ref "Pi") (pin "40") (pinfunction "40_40") (pintype "passive"))
      (node (ref "Pi") (pin "5") (pinfunction "5_5") (pintype "passive"))
      (node (ref "R10") (pin "2") (pinfunction "2_2") (pintype "passive"))
      (node (ref "R13") (pin "1") (pinfunction "1_1") (pintype "passive"))
      (node (ref "R14") (pin "2") (pinfunction "2_2") (pintype "passive"))
      (node (ref "R5") (pin "2") (pinfunction "2_2") (pintype "passive"))
      (node (ref "R6") (pin "2") (pinfunction "2_2") (pintype "passive"))
      (node (ref "R9") (pin "2") (pinfunction "2_2") (pintype "passive"))
      (node (ref "T3") (pin "2") (pinfunction "S_2") (pintype "passive"))
      (node (ref "TP5") (pin "1") (pinfunction "1_1") (pintype "passive"))
      (node (ref "U1") (pin "2") (pinfunction "Vss_2") (pintype "passive"))
      (node (ref "U2") (pin "10") (pinfunction "AGND_10") (pintype "power_in"))
      (node (ref "U2") (pin "15") (pinfunction "AGND_15") (pintype "power_in"))
      (node (ref "U2") (pin "20") (pinfunction "ADR1_20") (pintype "input"))
      (node (ref "U2") (pin "26") (pinfunction "ADR0_26") (pintype "input"))
      (node (ref "U2") (pin "29") (pinfunction "DGND_29") (pintype "power_in"))
      (node (ref "U2") (pin "3") (pinfunction "PGND_3") (pintype "power_in"))
      (node (ref "U2") (pin "33") (pinfunction "GND_33") (pintype "power_in"))
      (node (ref "U2") (pin "40") (pinfunction "PGND_40") (pintype "power_in"))
      (node (ref "U2") (pin "46") (pinfunction "PGND_46") (pintype "power_in"))
      (node (ref "U2") (pin "49") (pinfunction "TH_GND_49") (pintype "passive"))
      (node (ref "U301") (pin "4") (pinfunction "GND_4") (pintype "power_in"))
      (node (ref "U301") (pin "9") (pinfunction "EPAD_9") (pintype "power_in"))
    )
    (net (code "40") (name "Net-(C25-Pad2)") (class "Default")
      (node (ref "C25") (pin "2") (pinfunction "2_2") (pintype "passive"))
      (node (ref "L1") (pin "2") (pinfunction "2_2") (pintype "passive"))
      (node (ref "P1") (pin "2") (pinfunction "2_2") (pintype "passive"))
    )
    (net (code "41") (name "Net-(C26-Pad2)") (class "Default")
      (node (ref "C26") (pin "2") (pinfunction "2_2") (pintype "passive"))
      (node (ref "L2") (pin "2") (pinfunction "2_2") (pintype "passive"))
      (node (ref "P1") (pin "1") (pinfunction "1_1") (pintype "passive"))
    )
    (net (code "42") (name "Net-(C27-Pad2)") (class "Default")
      (node (ref "C27") (pin "2") (pinfunction "2_2") (pintype "passive"))
      (node (ref "L3") (pin "2") (pinfunction "2_2") (pintype "passive"))
      (node (ref "P2") (pin "2") (pinfunction "2_2") (pintype "passive"))
    )
    (net (code "43") (name "Net-(C28-Pad2)") (class "Default")
      (node (ref "C28") (pin "2") (pinfunction "2_2") (pintype "passive"))
      (node (ref "L4") (pin "2") (pinfunction "2_2") (pintype "passive"))
      (node (ref "P2") (pin "1") (pinfunction "1_1") (pintype "passive"))
    )
    (net (code "44") (name "Net-(C38-Pad1)") (class "Default")
      (node (ref "C38") (pin "1") (pinfunction "1_1") (pintype "passive"))
      (node (ref "R9") (pin "1") (pinfunction "1_1") (pintype "passive"))
    )
    (net (code "45") (name "Net-(D2-A)") (class "Default")
      (node (ref "D2") (pin "2") (pinfunction "A_2") (pintype "passive"))
      (node (ref "P6") (pin "1") (pinfunction "1_1") (pintype "passive"))
      (node (ref "T3") (pin "3") (pinfunction "D_3") (pintype "passive"))
    )
    (net (code "46") (name "Net-(R5-Pad1)") (class "Default")
      (node (ref "R5") (pin "1") (pinfunction "1_1") (pintype "passive"))
      (node (ref "T2") (pin "1") (pinfunction "B_1") (pintype "passive"))
      (node (ref "T2") (pin "2") (pinfunction "C_2") (pintype "passive"))
      (node (ref "T2") (pin "3") (pinfunction "B_3") (pintype "passive"))
    )
    (net (code "47") (name "Net-(T1-G)") (class "Default")
      (node (ref "R6") (pin "1") (pinfunction "1_1") (pintype "passive"))
      (node (ref "T1") (pin "1") (pinfunction "G_1") (pintype "passive"))
      (node (ref "T2") (pin "4") (pinfunction "C_4") (pintype "passive"))
    )
    (net (code "48") (name "Net-(T3-G)") (class "Default")
      (node (ref "R17") (pin "1") (pinfunction "1_1") (pintype "passive"))
      (node (ref "T3") (pin "1") (pinfunction "G_1") (pintype "passive"))
    )
    (net (code "49") (name "Net-(U2-BSTRPA+)") (class "Default")
      (node (ref "C22") (pin "2") (pinfunction "2_2") (pintype "passive"))
      (node (ref "U2") (pin "5") (pinfunction "BSTRPA+_5") (pintype "passive"))
    )
    (net (code "50") (name "Net-(U2-BSTRPA-)") (class "Default")
      (node (ref "C17") (pin "2") (pinfunction "2_2") (pintype "passive"))
      (node (ref "U2") (pin "1") (pinfunction "BSTRPA-_1") (pintype "passive"))
    )
    (net (code "51") (name "Net-(U2-BSTRPB+)") (class "Default")
      (node (ref "C24") (pin "2") (pinfunction "2_2") (pintype "passive"))
      (node (ref "U2") (pin "44") (pinfunction "BSTRPB+_44") (pintype "passive"))
    )
    (net (code "52") (name "Net-(U2-BSTRPB-)") (class "Default")
      (node (ref "C23") (pin "2") (pinfunction "2_2") (pintype "passive"))
      (node (ref "U2") (pin "48") (pinfunction "BSTRPB-_48") (pintype "passive"))
    )
    (net (code "53") (name "Net-(U2-CN)") (class "Default")
      (node (ref "C12") (pin "2") (pinfunction "2_2") (pintype "passive"))
      (node (ref "U2") (pin "34") (pinfunction "CN_34") (pintype "passive"))
    )
    (net (code "54") (name "Net-(U2-CP)") (class "Default")
      (node (ref "C12") (pin "1") (pinfunction "1_1") (pintype "passive"))
      (node (ref "U2") (pin "32") (pinfunction "CP_32") (pintype "passive"))
    )
    (net (code "55") (name "Net-(U2-CPVSS)") (class "Default")
      (node (ref "C13") (pin "1") (pinfunction "1_1") (pintype "passive"))
      (node (ref "U2") (pin "35") (pinfunction "CPVSS_35") (pintype "passive"))
    )
    (net (code "56") (name "Net-(U2-DAC_OUTA)") (class "Default")
      (node (ref "C14") (pin "1") (pinfunction "1_1") (pintype "passive"))
      (node (ref "U2") (pin "13") (pinfunction "DAC_OUTA_13") (pintype "passive"))
    )
    (net (code "57") (name "Net-(U2-DAC_OUTB)") (class "Default")
      (node (ref "C18") (pin "1") (pinfunction "1_1") (pintype "passive"))
      (node (ref "U2") (pin "36") (pinfunction "DAC_OUTB_36") (pintype "passive"))
    )
    (net (code "58") (name "Net-(U2-DVDD_REG)") (class "Default")
      (node (ref "C16") (pin "1") (pinfunction "1_1") (pintype "passive"))
      (node (ref "U2") (pin "28") (pinfunction "DVDD_REG_28") (pintype "power_in"))
    )
    (net (code "59") (name "Net-(U2-GVDD_REG)") (class "Default")
      (node (ref "C2") (pin "1") (pinfunction "1_1") (pintype "passive"))
      (node (ref "R4") (pin "2") (pinfunction "2_2") (pintype "passive"))
      (node (ref "U2") (pin "8") (pinfunction "GVDD_REG_8") (pintype "power_in"))
    )
    (net (code "60") (name "Net-(U2-SPK_GAIN{slash}FREQ)") (class "Default")
      (node (ref "R13") (pin "2") (pinfunction "2_2") (pintype "passive"))
      (node (ref "R4") (pin "1") (pinfunction "1_1") (pintype "passive"))
      (node (ref "U2") (pin "9") (pinfunction "SPK_GAIN/FREQ_9") (pintype "passive"))
    )
    (net (code "61") (name "Net-(U2-SPK_INA+)") (class "Default")
      (node (ref "C14") (pin "2") (pinfunction "2_2") (pintype "passive"))
      (node (ref "U2") (pin "12") (pinfunction "SPK_INA+_12") (pintype "passive"))
    )
    (net (code "62") (name "Net-(U2-SPK_INA-)") (class "Default")
      (node (ref "C15") (pin "2") (pinfunction "2_2") (pintype "passive"))
      (node (ref "U2") (pin "11") (pinfunction "SPK_INA-_11") (pintype "passive"))
    )
    (net (code "63") (name "Net-(U2-SPK_INB+)") (class "Default")
      (node (ref "C18") (pin "2") (pinfunction "2_2") (pintype "passive"))
      (node (ref "U2") (pin "37") (pinfunction "SPK_INB+_37") (pintype "passive"))
    )
    (net (code "64") (name "Net-(U2-SPK_INB-)") (class "Default")
      (node (ref "C19") (pin "2") (pinfunction "2_2") (pintype "passive"))
      (node (ref "U2") (pin "38") (pinfunction "SPK_INB-_38") (pintype "passive"))
    )
    (net (code "65") (name "Net-(U2-SPK_OUTA+)") (class "Default")
      (node (ref "C22") (pin "1") (pinfunction "1_1") (pintype "passive"))
      (node (ref "L3") (pin "1") (pinfunction "1_1") (pintype "passive"))
      (node (ref "U2") (pin "4") (pinfunction "SPK_OUTA+_4") (pintype "passive"))
    )
    (net (code "66") (name "Net-(U2-SPK_OUTA-)") (class "Default")
      (node (ref "C17") (pin "1") (pinfunction "1_1") (pintype "passive"))
      (node (ref "L4") (pin "1") (pinfunction "1_1") (pintype "passive"))
      (node (ref "U2") (pin "2") (pinfunction "SPK_OUTA-_2") (pintype "passive"))
    )
    (net (code "67") (name "Net-(U2-SPK_OUTB+)") (class "Default")
      (node (ref "C24") (pin "1") (pinfunction "1_1") (pintype "passive"))
      (node (ref "L2") (pin "1") (pinfunction "1_1") (pintype "passive"))
      (node (ref "U2") (pin "45") (pinfunction "SPK_OUTB+_45") (pintype "passive"))
    )
    (net (code "68") (name "Net-(U2-SPK_OUTB-)") (class "Default")
      (node (ref "C23") (pin "1") (pinfunction "1_1") (pintype "passive"))
      (node (ref "L1") (pin "1") (pinfunction "1_1") (pintype "passive"))
      (node (ref "U2") (pin "47") (pinfunction "SPK_OUTB-_47") (pintype "passive"))
    )
    (net (code "69") (name "Net-(U301-BOOT)") (class "Default")
      (node (ref "C20") (pin "1") (pinfunction "1_1") (pintype "passive"))
      (node (ref "U301") (pin "2") (pinfunction "BOOT_2") (pintype "passive"))
    )
    (net (code "70") (name "Net-(U301-COMP)") (class "Default")
      (node (ref "C38") (pin "2") (pinfunction "2_2") (pintype "passive"))
      (node (ref "U301") (pin "6") (pinfunction "COMP_6") (pintype "passive"))
    )
    (net (code "71") (name "Net-(U301-EN)") (class "Default")
      (node (ref "R7") (pin "1") (pinfunction "1_1") (pintype "passive"))
      (node (ref "U301") (pin "3") (pinfunction "EN_3") (pintype "input"))
    )
    (net (code "72") (name "Net-(U301-FB)") (class "Default")
      (node (ref "R14") (pin "1") (pinfunction "1_1") (pintype "passive"))
      (node (ref "R8") (pin "2") (pinfunction "2_2") (pintype "passive"))
      (node (ref "U301") (pin "5") (pinfunction "FB_5") (pintype "passive"))
    )
    (net (code "73") (name "Net-(U301-RLIM)") (class "Default")
      (node (ref "R10") (pin "1") (pinfunction "1_1") (pintype "passive"))
      (node (ref "U301") (pin "7") (pinfunction "RLIM_7") (pintype "passive"))
    )
    (net (code "74") (name "Net-(U301-SW)") (class "Default")
      (node (ref "C20") (pin "2") (pinfunction "2_2") (pintype "passive"))
      (node (ref "L5") (pin "1") (pinfunction "1_1") (pintype "passive"))
      (node (ref "U301") (pin "1") (pinfunction "SW_1") (pintype "passive"))
    )
    (net (code "75") (name "PVDD") (class "Default")
      (node (ref "C21") (pin "1") (pinfunction "1_1") (pintype "passive"))
      (node (ref "C29") (pin "1") (pinfunction "1_1") (pintype "passive"))
      (node (ref "C3") (pin "1") (pinfunction "1_1") (pintype "passive"))
      (node (ref "C32") (pin "1") (pinfunction "1_1") (pintype "passive"))
      (node (ref "C33") (pin "1") (pinfunction "1_1") (pintype "passive"))
      (node (ref "C34") (pin "1") (pinfunction "1_1") (pintype "passive"))
      (node (ref "C35") (pin "1") (pinfunction "1_1") (pintype "passive"))
      (node (ref "C39") (pin "1") (pinfunction "1_1") (pintype "passive"))
      (node (ref "C4") (pin "1") (pinfunction "1_1") (pintype "passive"))
      (node (ref "C40") (pin "1") (pinfunction "1_1") (pintype "passive"))
      (node (ref "C5") (pin "1") (pinfunction "1_1") (pintype "passive"))
      (node (ref "C6") (pin "1") (pinfunction "1_1") (pintype "passive"))
      (node (ref "C7") (pin "1") (pinfunction "1_1") (pintype "passive"))
      (node (ref "C8") (pin "1") (pinfunction "1_1") (pintype "passive"))
      (node (ref "D2") (pin "1") (pinfunction "C_1") (pintype "passive"))
      (node (ref "P3") (pin "1") (pinfunction "1_1") (pintype "passive"))
      (node (ref "P6") (pin "2") (pinfunction "2_2") (pintype "passive"))
      (node (ref "R7") (pin "2") (pinfunction "2_2") (pintype "passive"))
      (node (ref "U2") (pin "41") (pinfunction "PVDD_41") (pintype "power_in"))
      (node (ref "U2") (pin "42") (pinfunction "PVDD_42") (pintype "power_in"))
      (node (ref "U2") (pin "43") (pinfunction "PVDD_43") (pintype "power_in"))
      (node (ref "U2") (pin "6") (pinfunction "PVDD_6") (pintype "power_in"))
      (node (ref "U2") (pin "7") (pinfunction "PVDD_7") (pintype "power_in"))
      (node (ref "U301") (pin "8") (pinfunction "VIN_8") (pintype "power_in"))
    )
  )
)
